# DF12_32-to-header-pins.net
KiCad netlist of a schematic drawn in EAGLE
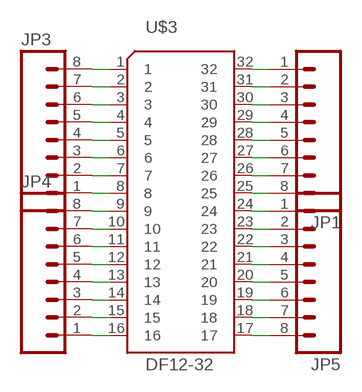
[diagram p0: schematic, sheet 1]

(export (version "E")
  (design (tool "Eeschema 10.0.6"))
  (components
    (comp (ref "JP1")
      (value "M081X08")
      (footprint "eagle-import:1X08")
      (libsource (lib "eagle-import") (part "M081X08"))
    )
    (comp (ref "JP3")
      (value "M081X08")
      (footprint "eagle-import:1X08")
      (libsource (lib "eagle-import") (part "M081X08"))
    )
    (comp (ref "JP4")
      (value "M081X08")
      (footprint "eagle-import:1X08")
      (libsource (lib "eagle-import") (part "M081X08"))
    )
    (comp (ref "JP5")
      (value "M081X08")
      (footprint "eagle-import:1X08")
      (libsource (lib "eagle-import") (part "M081X08"))
    )
    (comp (ref "U$3")
      (value "DF12-32")
      (footprint "eagle-import:DF12-32")
      (libsource (lib "eagle-import") (part "DF12-32"))
    )
  )
  (nets
    (net (code "1") (name "Net-(JP1-Pad1)") (class "Default")
      (node (ref "JP1") (pin "1") (pinfunction "1_1") (pintype "passive"))
      (node (ref "U$3") (pin "32") (pinfunction "32_32") (pintype "bidirectional"))
    )
    (net (code "2") (name "Net-(JP1-Pad2)") (class "Default")
      (node (ref "JP1") (pin "2") (pinfunction "2_2") (pintype "passive"))
      (node (ref "U$3") (pin "31") (pinfunction "31_31") (pintype "bidirectional"))
    )
    (net (code "3") (name "Net-(JP1-Pad3)") (class "Default")
      (node (ref "JP1") (pin "3") (pinfunction "3_3") (pintype "passive"))
      (node (ref "U$3") (pin "30") (pinfunction "30_30") (pintype "bidirectional"))
    )
    (net (code "4") (name "Net-(JP1-Pad4)") (class "Default")
      (node (ref "JP1") (pin "4") (pinfunction "4_4") (pintype "passive"))
      (node (ref "U$3") (pin "29") (pinfunction "29_29") (pintype "bidirectional"))
    )
    (net (code "5") (name "Net-(JP1-Pad5)") (class "Default")
      (node (ref "JP1") (pin "5") (pinfunction "5_5") (pintype "passive"))
      (node (ref "U$3") (pin "28") (pinfunction "28_28") (pintype "bidirectional"))
    )
    (net (code "6") (name "Net-(JP1-Pad6)") (class "Default")
      (node (ref "JP1") (pin "6") (pinfunction "6_6") (pintype "passive"))
      (node (ref "U$3") (pin "27") (pinfunction "27_27") (pintype "bidirectional"))
    )
    (net (code "7") (name "Net-(JP1-Pad7)") (class "Default")
      (node (ref "JP1") (pin "7") (pinfunction "7_7") (pintype "passive"))
      (node (ref "U$3") (pin "26") (pinfunction "26_26") (pintype "bidirectional"))
    )
    (net (code "8") (name "Net-(JP1-Pad8)") (class "Default")
      (node (ref "JP1") (pin "8") (pinfunction "8_8") (pintype "passive"))
      (node (ref "U$3") (pin "25") (pinfunction "25_25") (pintype "bidirectional"))
    )
    (net (code "9") (name "Net-(JP3-Pad1)") (class "Default")
      (node (ref "JP3") (pin "1") (pinfunction "1_1") (pintype "passive"))
      (node (ref "U$3") (pin "8") (pinfunction "8_8") (pintype "bidirectional"))
    )
    (net (code "10") (name "Net-(JP3-Pad2)") (class "Default")
      (node (ref "JP3") (pin "2") (pinfunction "2_2") (pintype "passive"))
      (node (ref "U$3") (pin "7") (pinfunction "7_7") (pintype "bidirectional"))
    )
    (net (code "11") (name "Net-(JP3-Pad3)") (class "Default")
      (node (ref "JP3") (pin "3") (pinfunction "3_3") (pintype "passive"))
      (node (ref "U$3") (pin "6") (pinfunction "6_6") (pintype "bidirectional"))
    )
    (net (code "12") (name "Net-(JP3-Pad4)") (class "Default")
      (node (ref "JP3") (pin "4") (pinfunction "4_4") (pintype "passive"))
      (node (ref "U$3") (pin "5") (pinfunction "5_5") (pintype "bidirectional"))
    )
    (net (code "13") (name "Net-(JP3-Pad5)") (class "Default")
      (node (ref "JP3") (pin "5") (pinfunction "5_5") (pintype "passive"))
      (node (ref "U$3") (pin "4") (pinfunction "4_4") (pintype "bidirectional"))
    )
    (net (code "14") (name "Net-(JP3-Pad6)") (class "Default")
      (node (ref "JP3") (pin "6") (pinfunction "6_6") (pintype "passive"))
      (node (ref "U$3") (pin "3") (pinfunction "3_3") (pintype "bidirectional"))
    )
    (net (code "15") (name "Net-(JP3-Pad7)") (class "Default")
      (node (ref "JP3") (pin "7") (pinfunction "7_7") (pintype "passive"))
      (node (ref "U$3") (pin "2") (pinfunction "2_2") (pintype "bidirectional"))
    )
    (net (code "16") (name "Net-(JP3-Pad8)") (class "Default")
      (node (ref "JP3") (pin "8") (pinfunction "8_8") (pintype "passive"))
      (node (ref "U$3") (pin "1") (pinfunction "1_1") (pintype "bidirectional"))
    )
    (net (code "17") (name "Net-(JP4-Pad1)") (class "Default")
      (node (ref "JP4") (pin "1") (pinfunction "1_1") (pintype "passive"))
      (node (ref "U$3") (pin "16") (pinfunction "16_16") (pintype "bidirectional"))
    )
    (net (code "18") (name "Net-(JP4-Pad2)") (class "Default")
      (node (ref "JP4") (pin "2") (pinfunction "2_2") (pintype "passive"))
      (node (ref "U$3") (pin "15") (pinfunction "15_15") (pintype "bidirectional"))
    )
    (net (code "19") (name "Net-(JP4-Pad3)") (class "Default")
      (node (ref "JP4") (pin "3") (pinfunction "3_3") (pintype "passive"))
      (node (ref "U$3") (pin "14") (pinfunction "14_14") (pintype "bidirectional"))
    )
    (net (code "20") (name "Net-(JP4-Pad4)") (class "Default")
      (node (ref "JP4") (pin "4") (pinfunction "4_4") (pintype "passive"))
      (node (ref "U$3") (pin "13") (pinfunction "13_13") (pintype "bidirectional"))
    )
    (net (code "21") (name "Net-(JP4-Pad5)") (class "Default")
      (node (ref "JP4") (pin "5") (pinfunction "5_5") (pintype "passive"))
      (node (ref "U$3") (pin "12") (pinfunction "12_12") (pintype "bidirectional"))
    )
    (net (code "22") (name "Net-(JP4-Pad6)") (class "Default")
      (node (ref "JP4") (pin "6") (pinfunction "6_6") (pintype "passive"))
      (node (ref "U$3") (pin "11") (pinfunction "11_11") (pintype "bidirectional"))
    )
    (net (code "23") (name "Net-(JP4-Pad7)") (class "Default")
      (node (ref "JP4") (pin "7") (pinfunction "7_7") (pintype "passive"))
      (node (ref "U$3") (pin "10") (pinfunction "10_10") (pintype "bidirectional"))
    )
    (net (code "24") (name "Net-(JP4-Pad8)") (class "Default")
      (node (ref "JP4") (pin "8") (pinfunction "8_8") (pintype "passive"))
      (node (ref "U$3") (pin "9") (pinfunction "9_9") (pintype "bidirectional"))
    )
    (net (code "25") (name "Net-(JP5-Pad1)") (class "Default")
      (node (ref "JP5") (pin "1") (pinfunction "1_1") (pintype "passive"))
      (node (ref "U$3") (pin "24") (pinfunction "24_24") (pintype "bidirectional"))
    )
    (net (code "26") (name "Net-(JP5-Pad2)") (class "Default")
      (node (ref "JP5") (pin "2") (pinfunction "2_2") (pintype "passive"))
      (node (ref "U$3") (pin "23") (pinfunction "23_23") (pintype "bidirectional"))
    )
    (net (code "27") (name "Net-(JP5-Pad3)") (class "Default")
      (node (ref "JP5") (pin "3") (pinfunction "3_3") (pintype "passive"))
      (node (ref "U$3") (pin "22") (pinfunction "22_22") (pintype "bidirectional"))
    )
    (net (code "28") (name "Net-(JP5-Pad4)") (class "Default")
      (node (ref "JP5") (pin "4") (pinfunction "4_4") (pintype "passive"))
      (node (ref "U$3") (pin "21") (pinfunction "21_21") (pintype "bidirectional"))
    )
    (net (code "29") (name "Net-(JP5-Pad5)") (class "Default")
      (node (ref "JP5") (pin "5") (pinfunction "5_5") (pintype "passive"))
      (node (ref "U$3") (pin "20") (pinfunction "20_20") (pintype "bidirectional"))
    )
    (net (code "30") (name "Net-(JP5-Pad6)") (class "Default")
      (node (ref "JP5") (pin "6") (pinfunction "6_6") (pintype "passive"))
      (node (ref "U$3") (pin "19") (pinfunction "19_19") (pintype "bidirectional"))
    )
    (net (code "31") (name "Net-(JP5-Pad7)") (class "Default")
      (node (ref "JP5") (pin "7") (pinfunction "7_7") (pintype "passive"))
      (node (ref "U$3") (pin "18") (pinfunction "18_18") (pintype "bidirectional"))
    )
    (net (code "32") (name "Net-(JP5-Pad8)") (class "Default")
      (node (ref "JP5") (pin "8") (pinfunction "8_8") (pintype "passive"))
      (node (ref "U$3") (pin "17") (pinfunction "17_17") (pintype "bidirectional"))
    )
  )
)
